# wifi_ESP8266.net
KiCad netlist of a schematic drawn in Altium Designer
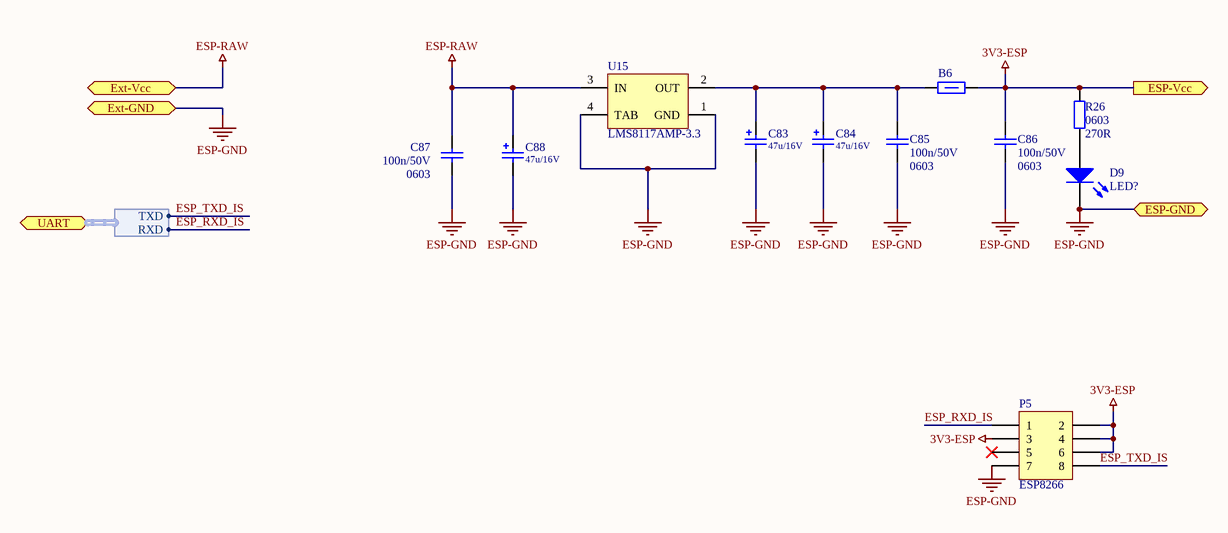
[diagram p0: wifi_ESP8266.SchDoc]

(export (version "E")
  (design (tool "Eeschema 10.0.6"))
  (components
    (comp (ref "B6")
      (value "120R/100MHz")
      (footprint "SMD_FerriteBead_1206")
      (description "Ferrite bead, 1206, 0.02HM, 3.5A.")
      (fields (field (name "MANUFACTURER") "Murata") (field (name "MANUFACTURERPARTNUMBER") "BLM31PG121SH1L"))
      (libsource (lib "inductors") (part "BLM31PG121SH1L"))
    )
    (comp (ref "C83")
      (value "47u/16V")
      (footprint "Tantalum_cap_B")
      (description "Tantalum Capacitor")
      (libsource (lib "GG") (part "Cap Tantalum"))
    )
    (comp (ref "C84")
      (value "47u/16V")
      (footprint "Tantalum_cap_B")
      (description "Tantalum Capacitor")
      (libsource (lib "GG") (part "Cap Tantalum"))
    )
    (comp (ref "C85")
      (value "100n/50V")
      (footprint "SMD_Capacitor_0603")
      (description "Ceramic Cap Kemet COTS 100n/50V X7R 0603")
      (fields
        (field (name "MANUFACTURER") "Kemet")
        (field (name "MANUFACTURERPARTNUMBER") "C0603T104K5RALTU")
        (field (name "PACKAGE") "0603")
      )
      (libsource (lib "capacitors") (part "Cer_C0603T104K5RALTU"))
    )
    (comp (ref "C86")
      (value "100n/50V")
      (footprint "SMD_Capacitor_0603")
      (description "Ceramic Cap Kemet COTS 100n/50V X7R 0603")
      (fields
        (field (name "MANUFACTURER") "Kemet")
        (field (name "MANUFACTURERPARTNUMBER") "C0603T104K5RALTU")
        (field (name "PACKAGE") "0603")
      )
      (libsource (lib "capacitors") (part "Cer_C0603T104K5RALTU"))
    )
    (comp (ref "C87")
      (value "100n/50V")
      (footprint "SMD_Capacitor_0603")
      (description "Ceramic Cap Kemet COTS 100n/50V X7R 0603")
      (fields
        (field (name "MANUFACTURER") "Kemet")
        (field (name "MANUFACTURERPARTNUMBER") "C0603T104K5RALTU")
        (field (name "PACKAGE") "0603")
      )
      (libsource (lib "capacitors") (part "Cer_C0603T104K5RALTU"))
    )
    (comp (ref "C88")
      (value "47u/16V")
      (footprint "Tantalum_cap_B")
      (description "Tantalum Capacitor")
      (libsource (lib "GG") (part "Cap Tantalum"))
    )
    (comp (ref "D9")
      (value "LED?")
      (footprint "LED 0805 RED")
      (description "Typical BLUE SiC LED")
      (fields (field (name "PUBLISHER") "Altium Limited"))
      (libsource (lib "Miscellaneous Devices") (part "LED3"))
    )
    (comp (ref "P5")
      (value "ESP8266")
      (footprint "HEADER 2X4 FEMALE")
      (description "Header, 4-Pin, Dual row")
      (fields (field (name "PUBLISHER") "Altium Limited"))
      (libsource (lib "GG") (part "Header 4X2"))
    )
    (comp (ref "R26")
      (value "0603")
      (footprint "SMD_Resistor_0603")
      (description "Resistor")
      (fields (field (name "ALTIUM_VALUE") "270R") (field (name "PUBLISHER") "Altium Limited"))
      (libsource (lib "Miscellaneous Devices") (part "Res2"))
    )
    (comp (ref "U15")
      (value "LMS8117AMP-3.3")
      (footprint "MP04A_M")
      (description "1A Low-Dropout Linear Regulator, 4-pin SOT-223")
      (fields (field (name "MANUFACTURER") "National Semiconductor"))
      (libsource (lib "National Semiconductor LDO") (part "LMS8117AMP-3.3"))
    )
  )
  (nets
    (net (code "2") (name "/ESP_RXD_IS") (class "Default")
      (node (ref "P5") (pin "1") (pinfunction "1_1") (pintype "passive"))
    )
    (net (code "3") (name "/ESP_TXD_IS") (class "Default")
      (node (ref "P5") (pin "8") (pinfunction "8_8") (pintype "passive"))
    )
    (net (code "5") (name "3V3-ESP") (class "Default")
      (node (ref "B6") (pin "2") (pinfunction "2_2") (pintype "passive"))
      (node (ref "C86") (pin "1") (pinfunction "1_1") (pintype "passive"))
      (node (ref "P5") (pin "2") (pinfunction "2_2") (pintype "passive"))
      (node (ref "P5") (pin "3") (pinfunction "3_3") (pintype "passive"))
      (node (ref "P5") (pin "4") (pinfunction "4_4") (pintype "passive"))
      (node (ref "P5") (pin "6") (pinfunction "6_6") (pintype "passive"))
      (node (ref "R26") (pin "1") (pinfunction "1_1") (pintype "passive"))
    )
    (net (code "6") (name "ESP-GND") (class "Default")
      (node (ref "C83") (pin "2") (pinfunction "2_2") (pintype "passive"))
      (node (ref "C84") (pin "2") (pinfunction "2_2") (pintype "passive"))
      (node (ref "C85") (pin "2") (pinfunction "2_2") (pintype "passive"))
      (node (ref "C86") (pin "2") (pinfunction "2_2") (pintype "passive"))
      (node (ref "C87") (pin "2") (pinfunction "2_2") (pintype "passive"))
      (node (ref "C88") (pin "2") (pinfunction "2_2") (pintype "passive"))
      (node (ref "D9") (pin "2") (pinfunction "K_2") (pintype "passive"))
      (node (ref "P5") (pin "7") (pinfunction "7_7") (pintype "passive"))
      (node (ref "U15") (pin "1") (pinfunction "GND_1") (pintype "power_in"))
      (node (ref "U15") (pin "4") (pinfunction "TAB_4") (pintype "power_in"))
    )
    (net (code "7") (name "ESP-RAW") (class "Default")
      (node (ref "C87") (pin "1") (pinfunction "1_1") (pintype "passive"))
      (node (ref "C88") (pin "1") (pinfunction "1_1") (pintype "passive"))
      (node (ref "U15") (pin "3") (pinfunction "IN_3") (pintype "power_in"))
    )
    (net (code "8") (name "Net-(D9-A)") (class "Default")
      (node (ref "D9") (pin "1") (pinfunction "A_1") (pintype "passive"))
      (node (ref "R26") (pin "2") (pinfunction "2_2") (pintype "passive"))
    )
    (net (code "9") (name "Net-(U15-OUT)") (class "Default")
      (node (ref "B6") (pin "1") (pinfunction "1_1") (pintype "passive"))
      (node (ref "C83") (pin "1") (pinfunction "1_1") (pintype "passive"))
      (node (ref "C84") (pin "1") (pinfunction "1_1") (pintype "passive"))
      (node (ref "C85") (pin "1") (pinfunction "1_1") (pintype "passive"))
      (node (ref "U15") (pin "2") (pinfunction "OUT_2") (pintype "power_in"))
    )
    (net (code "10") (name "unconnected-(P5-Pad5)") (class "Default")
      (node (ref "P5") (pin "5") (pinfunction "5_5") (pintype "passive+no_connect"))
    )
  )
)
